# 7-segment.net
KiCad netlist of a schematic drawn in EAGLE
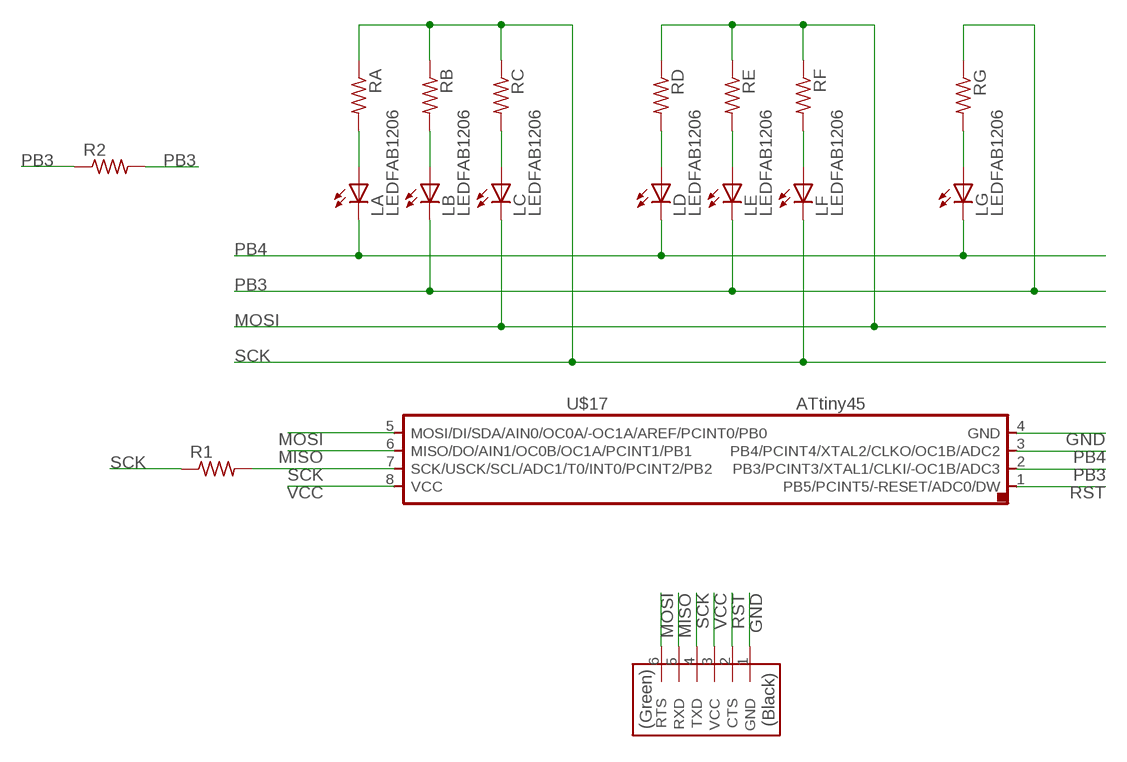
[diagram p0: schematic, sheet 1]

(export (version "E")
  (design (tool "Eeschema 10.0.6"))
  (components
    (comp (ref "LA")
      (value "LEDFAB1206")
      (footprint "eagle-import:LED1206FAB")
      (libsource (lib "eagle-import") (part "LEDFAB1206"))
    )
    (comp (ref "LB")
      (value "LEDFAB1206")
      (footprint "eagle-import:LED1206FAB")
      (libsource (lib "eagle-import") (part "LEDFAB1206"))
    )
    (comp (ref "LC")
      (value "LEDFAB1206")
      (footprint "eagle-import:LED1206FAB")
      (libsource (lib "eagle-import") (part "LEDFAB1206"))
    )
    (comp (ref "LD")
      (value "LEDFAB1206")
      (footprint "eagle-import:LED1206FAB")
      (libsource (lib "eagle-import") (part "LEDFAB1206"))
    )
    (comp (ref "LE")
      (value "LEDFAB1206")
      (footprint "eagle-import:LED1206FAB")
      (libsource (lib "eagle-import") (part "LEDFAB1206"))
    )
    (comp (ref "LF")
      (value "LEDFAB1206")
      (footprint "eagle-import:LED1206FAB")
      (libsource (lib "eagle-import") (part "LEDFAB1206"))
    )
    (comp (ref "LG")
      (value "LEDFAB1206")
      (footprint "eagle-import:LED1206FAB")
      (libsource (lib "eagle-import") (part "LEDFAB1206"))
    )
    (comp (ref "R1")
      (value "RES-US1206FAB")
      (footprint "eagle-import:R1206FAB")
      (libsource (lib "eagle-import") (part "RES-US1206FAB"))
    )
    (comp (ref "R2")
      (value "RES-US1206FAB")
      (footprint "eagle-import:R1206FAB")
      (libsource (lib "eagle-import") (part "RES-US1206FAB"))
    )
    (comp (ref "RA")
      (value "RES-US1206FAB")
      (footprint "eagle-import:R1206FAB")
      (libsource (lib "eagle-import") (part "RES-US1206FAB"))
    )
    (comp (ref "RB")
      (value "RES-US1206FAB")
      (footprint "eagle-import:R1206FAB")
      (libsource (lib "eagle-import") (part "RES-US1206FAB"))
    )
    (comp (ref "RC")
      (value "RES-US1206FAB")
      (footprint "eagle-import:R1206FAB")
      (libsource (lib "eagle-import") (part "RES-US1206FAB"))
    )
    (comp (ref "RD")
      (value "RES-US1206FAB")
      (footprint "eagle-import:R1206FAB")
      (libsource (lib "eagle-import") (part "RES-US1206FAB"))
    )
    (comp (ref "RE")
      (value "RES-US1206FAB")
      (footprint "eagle-import:R1206FAB")
      (libsource (lib "eagle-import") (part "RES-US1206FAB"))
    )
    (comp (ref "RF")
      (value "RES-US1206FAB")
      (footprint "eagle-import:R1206FAB")
      (libsource (lib "eagle-import") (part "RES-US1206FAB"))
    )
    (comp (ref "RG")
      (value "RES-US1206FAB")
      (footprint "eagle-import:R1206FAB")
      (libsource (lib "eagle-import") (part "RES-US1206FAB"))
    )
    (comp (ref "U$3")
      (value "FTDI-SMD-HEADER")
      (footprint "eagle-import:1X06SMD")
      (libsource (lib "eagle-import") (part "FTDI-SMD-HEADER"))
    )
    (comp (ref "U$17")
      (value "ATTINY45SI")
      (footprint "eagle-import:SOIC8")
      (libsource (lib "eagle-import") (part "ATTINY45SI"))
    )
  )
  (nets
    (net (code "1") (name "/GND") (class "Default")
      (node (ref "U$17") (pin "4") (pinfunction "GND_4") (pintype "bidirectional"))
      (node (ref "U$3") (pin "1") (pinfunction "GND_1") (pintype "bidirectional"))
    )
    (net (code "2") (name "/MISO") (class "Default")
      (node (ref "U$17") (pin "6") (pinfunction "MISO/DO/AIN1/OC0B/OC1A/PCINT1/PB1_6") (pintype "bidirectional"))
      (node (ref "U$3") (pin "5") (pinfunction "RXD_5") (pintype "bidirectional"))
    )
    (net (code "3") (name "/MOSI") (class "Default")
      (node (ref "LC") (pin "2") (pinfunction "C_2") (pintype "passive"))
      (node (ref "RD") (pin "1") (pinfunction "1_1") (pintype "passive"))
      (node (ref "RE") (pin "1") (pinfunction "1_1") (pintype "passive"))
      (node (ref "RF") (pin "1") (pinfunction "1_1") (pintype "passive"))
      (node (ref "U$17") (pin "5") (pinfunction "MOSI/DI/SDA/AIN0/OC0A/-OC1A/AREF/PCINT0/PB0_5") (pintype "bidirectional"))
      (node (ref "U$3") (pin "6") (pinfunction "RTS_6") (pintype "bidirectional"))
    )
    (net (code "4") (name "/PB3") (class "Default")
      (node (ref "LB") (pin "2") (pinfunction "C_2") (pintype "passive"))
      (node (ref "LE") (pin "2") (pinfunction "C_2") (pintype "passive"))
      (node (ref "R2") (pin "1") (pinfunction "1_1") (pintype "passive"))
      (node (ref "R2") (pin "2") (pinfunction "2_2") (pintype "passive"))
      (node (ref "RG") (pin "1") (pinfunction "1_1") (pintype "passive"))
      (node (ref "U$17") (pin "2") (pinfunction "PB3/PCINT3/XTAL1/CLKI/-OC1B/ADC3_2") (pintype "bidirectional"))
    )
    (net (code "5") (name "/PB4") (class "Default")
      (node (ref "LA") (pin "2") (pinfunction "C_2") (pintype "passive"))
      (node (ref "LD") (pin "2") (pinfunction "C_2") (pintype "passive"))
      (node (ref "LG") (pin "2") (pinfunction "C_2") (pintype "passive"))
      (node (ref "U$17") (pin "3") (pinfunction "PB4/PCINT4/XTAL2/CLKO/OC1B/ADC2_3") (pintype "bidirectional"))
    )
    (net (code "6") (name "/RST") (class "Default")
      (node (ref "U$17") (pin "1") (pinfunction "PB5/PCINT5/-RESET/ADC0/DW_1") (pintype "bidirectional"))
      (node (ref "U$3") (pin "2") (pinfunction "CTS_2") (pintype "bidirectional"))
    )
    (net (code "7") (name "/SCK") (class "Default")
      (node (ref "LF") (pin "2") (pinfunction "C_2") (pintype "passive"))
      (node (ref "R1") (pin "1") (pinfunction "1_1") (pintype "passive"))
      (node (ref "R1") (pin "2") (pinfunction "2_2") (pintype "passive"))
      (node (ref "RA") (pin "1") (pinfunction "1_1") (pintype "passive"))
      (node (ref "RB") (pin "1") (pinfunction "1_1") (pintype "passive"))
      (node (ref "RC") (pin "1") (pinfunction "1_1") (pintype "passive"))
      (node (ref "U$17") (pin "7") (pinfunction "SCK/USCK/SCL/ADC1/T0/INT0/PCINT2/PB2_7") (pintype "bidirectional"))
      (node (ref "U$3") (pin "4") (pinfunction "TXD_4") (pintype "bidirectional"))
    )
    (net (code "8") (name "/VCC") (class "Default")
      (node (ref "U$17") (pin "8") (pinfunction "VCC_8") (pintype "bidirectional"))
      (node (ref "U$3") (pin "3") (pinfunction "VCC_3") (pintype "bidirectional"))
    )
    (net (code "9") (name "Net-(LA-A)") (class "Default")
      (node (ref "LA") (pin "1") (pinfunction "A_1") (pintype "passive"))
      (node (ref "RA") (pin "2") (pinfunction "2_2") (pintype "passive"))
    )
    (net (code "10") (name "Net-(LB-A)") (class "Default")
      (node (ref "LB") (pin "1") (pinfunction "A_1") (pintype "passive"))
      (node (ref "RB") (pin "2") (pinfunction "2_2") (pintype "passive"))
    )
    (net (code "11") (name "Net-(LC-A)") (class "Default")
      (node (ref "LC") (pin "1") (pinfunction "A_1") (pintype "passive"))
      (node (ref "RC") (pin "2") (pinfunction "2_2") (pintype "passive"))
    )
    (net (code "12") (name "Net-(LD-A)") (class "Default")
      (node (ref "LD") (pin "1") (pinfunction "A_1") (pintype "passive"))
      (node (ref "RD") (pin "2") (pinfunction "2_2") (pintype "passive"))
    )
    (net (code "13") (name "Net-(LE-A)") (class "Default")
      (node (ref "LE") (pin "1") (pinfunction "A_1") (pintype "passive"))
      (node (ref "RE") (pin "2") (pinfunction "2_2") (pintype "passive"))
    )
    (net (code "14") (name "Net-(LF-A)") (class "Default")
      (node (ref "LF") (pin "1") (pinfunction "A_1") (pintype "passive"))
      (node (ref "RF") (pin "2") (pinfunction "2_2") (pintype "passive"))
    )
    (net (code "15") (name "Net-(LG-A)") (class "Default")
      (node (ref "LG") (pin "1") (pinfunction "A_1") (pintype "passive"))
      (node (ref "RG") (pin "2") (pinfunction "2_2") (pintype "passive"))
    )
  )
)
